# Control_Module_IO.net
KiCad netlist of a schematic drawn in Altium Designer
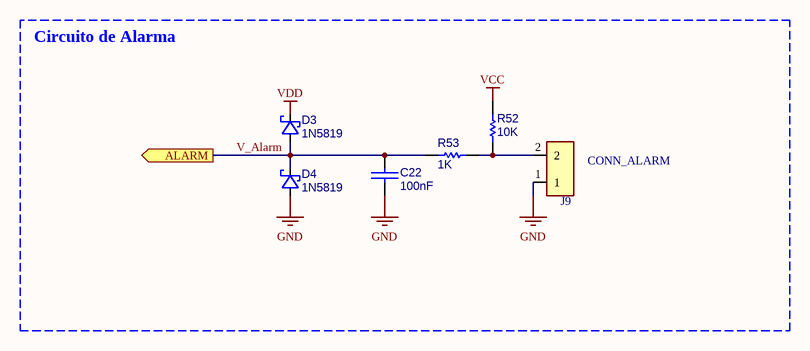
[diagram p0: Control_Module_IO.SchDoc]

(export (version "E")
  (design (tool "Eeschema 10.0.6"))
  (components
    (comp (ref "C22")
      (value "100nF")
      (footprint "CAP0402")
      (description "Non Polarized Capacitor")
      (libsource (lib "Control_Module_Symbols") (part "CAP"))
    )
    (comp (ref "D3")
      (value "1N5819")
      (footprint "SOD_123")
      (description "Diode Shottky")
      (libsource (lib "Control_Module_Symbols") (part "DIODO_SH"))
    )
    (comp (ref "D4")
      (value "1N5819")
      (footprint "SOD_123")
      (description "Diode Shottky")
      (libsource (lib "Control_Module_Symbols") (part "DIODO_SH"))
    )
    (comp (ref "J9")
      (value "CONN_ALARM")
      (footprint "TerminalBlock_1x2_P5mm")
      (libsource (lib "Control_Module_Symbols") (part "CONN_2P"))
    )
    (comp (ref "R52")
      (value "10K")
      (footprint "RES0402")
      (description "Resistor")
      (libsource (lib "Control_Module_Symbols") (part "Res1"))
    )
    (comp (ref "R53")
      (value "1K")
      (footprint "RES0402")
      (description "Resistor")
      (libsource (lib "Control_Module_Symbols") (part "Res1"))
    )
  )
  (nets
    (net (code "1") (name "/V_Alarm") (class "Default")
      (node (ref "C22") (pin "1") (pinfunction "1_1") (pintype "passive"))
      (node (ref "D3") (pin "1") (pinfunction "A_1") (pintype "passive"))
      (node (ref "D4") (pin "2") (pinfunction "K_2") (pintype "passive"))
      (node (ref "R53") (pin "1") (pinfunction "1_1") (pintype "passive"))
    )
    (net (code "2") (name "GND") (class "Default")
      (node (ref "C22") (pin "2") (pinfunction "2_2") (pintype "passive"))
      (node (ref "D4") (pin "1") (pinfunction "A_1") (pintype "passive"))
      (node (ref "J9") (pin "1") (pinfunction "1_1") (pintype "passive"))
    )
    (net (code "3") (name "Net-(J9-Pad2)") (class "Default")
      (node (ref "J9") (pin "2") (pinfunction "2_2") (pintype "passive"))
      (node (ref "R52") (pin "2") (pinfunction "2_2") (pintype "passive"))
      (node (ref "R53") (pin "2") (pinfunction "2_2") (pintype "passive"))
    )
    (net (code "4") (name "VCC") (class "Default")
      (node (ref "R52") (pin "1") (pinfunction "1_1") (pintype "passive"))
    )
    (net (code "5") (name "VDD") (class "Default")
      (node (ref "D3") (pin "2") (pinfunction "K_2") (pintype "passive"))
    )
  )
)
